# Power_Sheet.net
KiCad netlist of a schematic drawn in Altium Designer
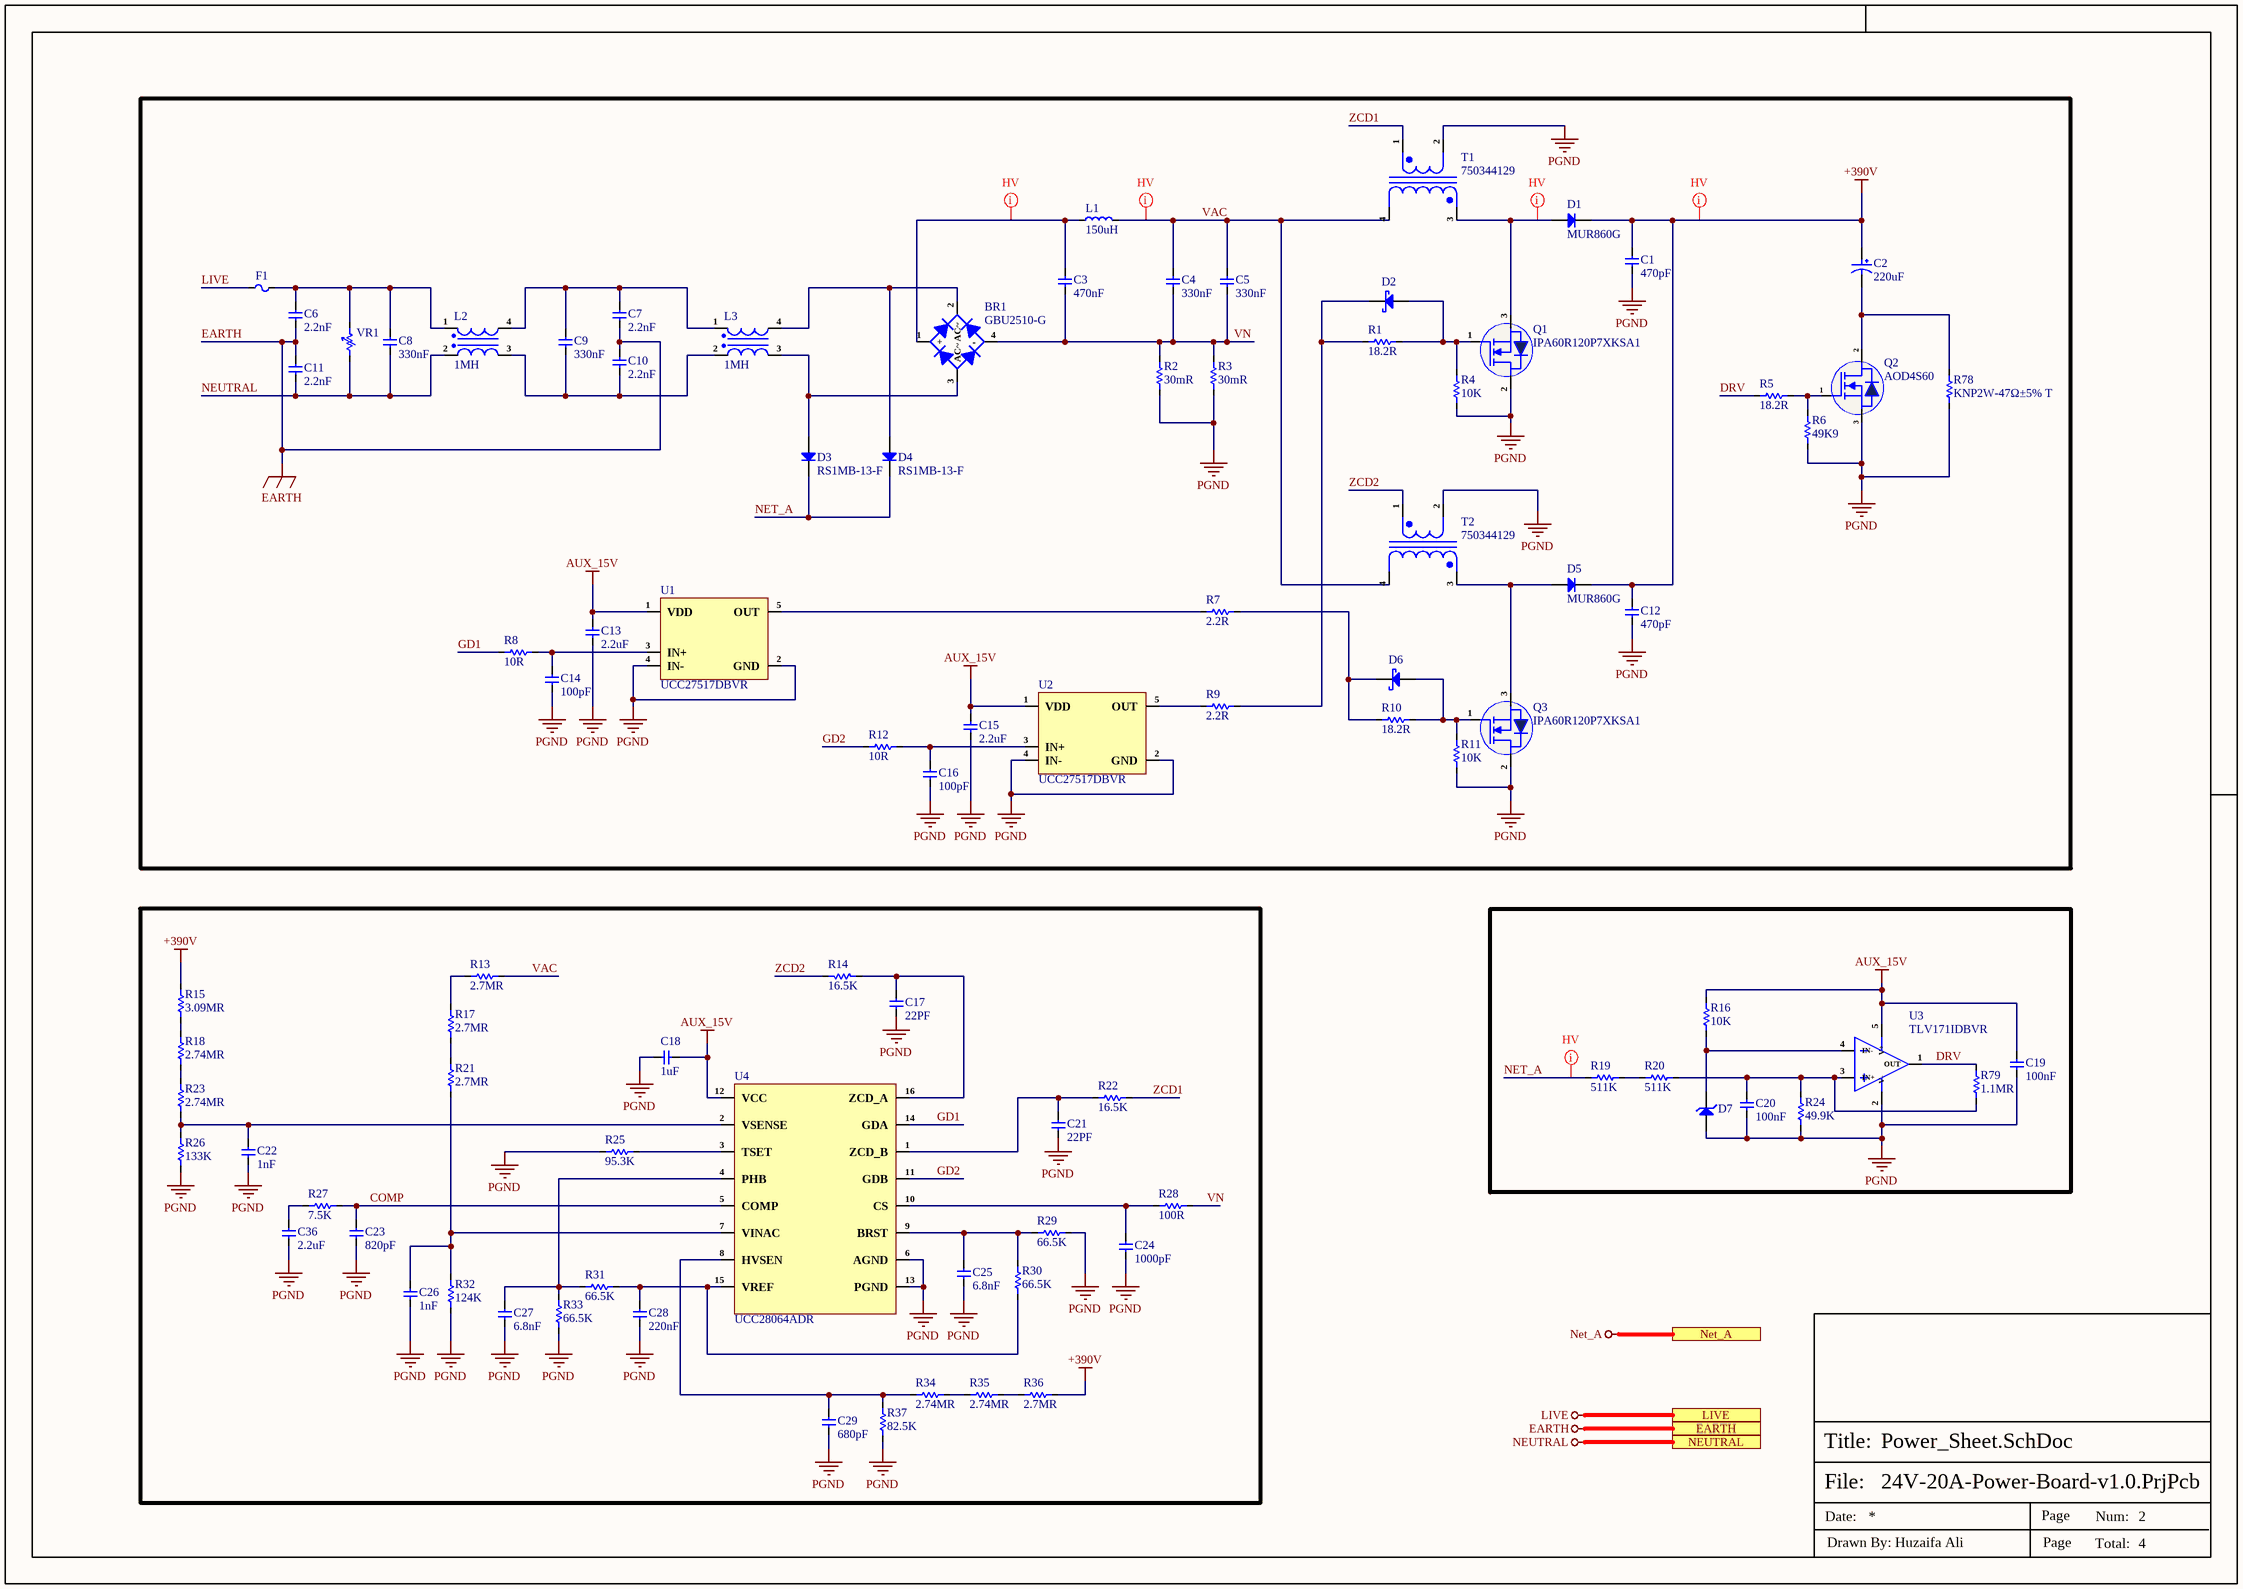
[diagram p0: Power_Sheet.SchDoc]

(export (version "E")
  (design (tool "Eeschema 10.0.6"))
  (components
    (comp (ref "BR1")
      (value "GBU2510-G")
      (footprint "GBU")
      (description "BRIDGE RECT 1PHASE 1KV 25A GBU")
      (fields (field (name "LCSC PART NUMBER") "C3012677") (field (name "MANUFACTURER") "Comchip"))
      (libsource (lib "eSpark Libraries") (part "GBU2510-G"))
    )
    (comp (ref "C1")
      (value "470pF")
      (footprint "Cap-0805")
      (description "CAP CER 470PF 500V X7R 0805")
      (fields (field (name "LCSC PART NUMBER") "C113867") (field (name "MANUFACTURER") "Yageo"))
      (libsource (lib "eSpark Libraries") (part "CC0805KRX7RBBB471"))
    )
    (comp (ref "C2")
      (value "220uF")
      (description "220uF 400V ±20% Plugin,D22xL40mm Aluminum Electrolytic Capacitors - Leaded ROHS")
      (fields
        (field (name "MANUFACTURER") "AISHI")
        (field (name "MANUFACTURER PART NUMBER") "EWH2GM221O40OT")
      )
      (libsource (lib "eSpark Libraries") (part "EWH2GM221O40OT"))
    )
    (comp (ref "C3")
      (value "470nF")
      (footprint "450MPK474J")
      (description "CAP FILM 0.47UF 5% 450VDC RADIAL")
      (fields (field (name "LCSC PART NUMBER") "C2798220") (field (name "MANUFACTURER") "Rubycon"))
      (libsource (lib "eSpark Libraries") (part "450MPK474J"))
    )
    (comp (ref "C4")
      (value "330nF")
      (footprint "MPP334J2J15AJ22800")
      (description "330nF -40℃~+105℃ ±5% 630V Plugin,P=15mm Polypropylene Film Capacitors (CBB) ROHS")
      (fields (field (name "LCSC PART NUMBER") "C506837") (field (name "MANUFACTURER") "KNSCHA"))
      (libsource (lib "eSpark Libraries") (part "MPP334J2J15AJ22800"))
    )
    (comp (ref "C5")
      (value "330nF")
      (footprint "MPP334J2J15AJ22800")
      (description "330nF -40℃~+105℃ ±5% 630V Plugin,P=15mm Polypropylene Film Capacitors (CBB) ROHS")
      (fields (field (name "LCSC PART NUMBER") "C506837") (field (name "MANUFACTURER") "KNSCHA"))
      (libsource (lib "eSpark Libraries") (part "MPP334J2J15AJ22800"))
    )
    (comp (ref "C6")
      (value "2.2nF")
      (footprint "AY1222M47Y5UC63L0")
      (description "CAP CER 2200PF 760VAC Y5U RADIAL")
      (fields (field (name "LCSC PART NUMBER") "C1620433"))
      (libsource (lib "eSpark Libraries") (part "AY1222M47Y5UC63L0"))
    )
    (comp (ref "C7")
      (value "2.2nF")
      (footprint "AY1222M47Y5UC63L0")
      (description "CAP CER 2200PF 760VAC Y5U RADIAL")
      (fields (field (name "LCSC PART NUMBER") "C1620433"))
      (libsource (lib "eSpark Libraries") (part "AY1222M47Y5UC63L0"))
    )
    (comp (ref "C8")
      (value "330nF")
      (description "330nF ±10% X2 Plugin,P=15mm Safety Capacitors ROHS")
      (fields
        (field (name "MANUFACTURER") "KNSCHA")
        (field (name "MANUFACTURER PART NUMBER") "MPX334K31D2KN15800")
      )
      (libsource (lib "eSpark Libraries") (part "MPX334K31D2KN15800"))
    )
    (comp (ref "C9")
      (value "330nF")
      (description "330nF ±10% X2 Plugin,P=15mm Safety Capacitors ROHS")
      (fields
        (field (name "MANUFACTURER") "KNSCHA")
        (field (name "MANUFACTURER PART NUMBER") "MPX334K31D2KN15800")
      )
      (libsource (lib "eSpark Libraries") (part "MPX334K31D2KN15800"))
    )
    (comp (ref "C10")
      (value "2.2nF")
      (footprint "AY1222M47Y5UC63L0")
      (description "CAP CER 2200PF 760VAC Y5U RADIAL")
      (fields (field (name "LCSC PART NUMBER") "C1620433"))
      (libsource (lib "eSpark Libraries") (part "AY1222M47Y5UC63L0"))
    )
    (comp (ref "C11")
      (value "2.2nF")
      (footprint "AY1222M47Y5UC63L0")
      (description "CAP CER 2200PF 760VAC Y5U RADIAL")
      (fields (field (name "LCSC PART NUMBER") "C1620433"))
      (libsource (lib "eSpark Libraries") (part "AY1222M47Y5UC63L0"))
    )
    (comp (ref "C12")
      (value "470pF")
      (footprint "Cap-0805")
      (description "CAP CER 470PF 500V X7R 0805")
      (fields (field (name "LCSC PART NUMBER") "C113867") (field (name "MANUFACTURER") "Yageo"))
      (libsource (lib "eSpark Libraries") (part "CC0805KRX7RBBB471"))
    )
    (comp (ref "C13")
      (value "2.2uF")
      (footprint "CAP-0603")
      (description "CAP CER 2.2UF 25V X5R 0603")
      (fields
        (field (name "MANUFACTURER") "Yageo")
        (field (name "MANUFACTURER PART NUMBER") "CC0603KRX5R8BB225")
      )
      (libsource (lib "eSpark Libraries") (part "CC0603KRX5R8BB225"))
    )
    (comp (ref "C14")
      (value "100pF")
      (footprint "Cap-0402")
      (description "CAP CER 100PF 50V C0G/NPO 0402")
      (fields
        (field (name "MANUFACTURER") "Yageo")
        (field (name "MANUFACTURER PART NUMBER") "CC0402JRNPO9BN101")
      )
      (libsource (lib "eSpark Libraries") (part "CC0402JRNPO9BN101"))
    )
    (comp (ref "C15")
      (value "2.2uF")
      (footprint "CAP-0603")
      (description "CAP CER 2.2UF 25V X5R 0603")
      (fields
        (field (name "MANUFACTURER") "Yageo")
        (field (name "MANUFACTURER PART NUMBER") "CC0603KRX5R8BB225")
      )
      (libsource (lib "eSpark Libraries") (part "CC0603KRX5R8BB225"))
    )
    (comp (ref "C16")
      (value "100pF")
      (footprint "Cap-0402")
      (description "CAP CER 100PF 50V C0G/NPO 0402")
      (fields
        (field (name "MANUFACTURER") "Yageo")
        (field (name "MANUFACTURER PART NUMBER") "CC0402JRNPO9BN101")
      )
      (libsource (lib "eSpark Libraries") (part "CC0402JRNPO9BN101"))
    )
    (comp (ref "C17")
      (value "22PF")
      (footprint "Cap-0402")
      (description "CAP CER 22PF 50V C0G/NPO 0402")
      (fields
        (field (name "MANUFACTURER") "Yageo")
        (field (name "MANUFACTURER PART NUMBER") "CC0402JRNPO9BN220")
      )
      (libsource (lib "eSpark Libraries") (part "CC0402JRNPO9BN220"))
    )
    (comp (ref "C18")
      (value "1uF")
      (footprint "Cap-0603")
      (description "CAP CER 1UF 25V X5R 0603")
      (fields
        (field (name "MANUFACTURER") "Yageo")
        (field (name "MANUFACTURER PART NUMBER") "CC0603KRX5R8BB105")
      )
      (libsource (lib "eSpark Libraries") (part "CC0603KRX5R8BB105"))
    )
    (comp (ref "C19")
      (value "100nF")
      (footprint "cap-0402")
      (description "CAP CER 0.1UF 50V X7R 0402")
      (fields
        (field (name "MANUFACTURER") "TDK")
        (field (name "MANUFACTURER PART NUMBER") "C1005X7R1H104KT000F")
      )
      (libsource (lib "eSpark Libraries") (part "C1005X7R1H104KT000F"))
    )
    (comp (ref "C20")
      (value "100nF")
      (footprint "cap-0402")
      (description "CAP CER 0.1UF 50V X7R 0402")
      (fields
        (field (name "MANUFACTURER") "TDK")
        (field (name "MANUFACTURER PART NUMBER") "C1005X7R1H104KT000F")
      )
      (libsource (lib "eSpark Libraries") (part "C1005X7R1H104KT000F"))
    )
    (comp (ref "C21")
      (value "22PF")
      (footprint "Cap-0402")
      (description "CAP CER 22PF 50V C0G/NPO 0402")
      (fields
        (field (name "MANUFACTURER") "Yageo")
        (field (name "MANUFACTURER PART NUMBER") "CC0402JRNPO9BN220")
      )
      (libsource (lib "eSpark Libraries") (part "CC0402JRNPO9BN220"))
    )
    (comp (ref "C22")
      (value "1nF")
      (footprint "Cap-0402")
      (description "CAP CER 1000PF 50V C0G/NP0 0402")
      (fields
        (field (name "MANUFACTURER") "Murata")
        (field (name "MANUFACTURER PART NUMBER") "GRM1555C1H102JA01D")
      )
      (libsource (lib "eSpark Libraries") (part "GRM1555C1H102JA01D"))
    )
    (comp (ref "C23")
      (value "820pF")
      (footprint "Cap-0603")
      (description "CAP CER 820PF 50V C0G/NPO 0603")
      (fields (field (name "LCSC PART NUMBER") "C107057") (field (name "MANUFACTURER") "Yageo"))
      (libsource (lib "eSpark Libraries") (part "CC0603JRNPO9BN821"))
    )
    (comp (ref "C24")
      (value "1000pF")
      (footprint "Cap-0603")
      (description "CAP CER 1000PF 50V C0G/NP0 0603")
      (fields
        (field (name "MANUFACTURER") "Samsung")
        (field (name "MANUFACTURER PART NUMBER") "CL10C102JB8NNNC")
      )
      (libsource (lib "eSpark Libraries") (part "CL10C102JB8NNNC"))
    )
    (comp (ref "C25")
      (value "6.8nF")
      (footprint "Cap-0603")
      (description "50V 6.8nF X7R ±10% 0603")
      (fields (field (name "MANUFACTURER") "FH") (field (name "MANUFACTURER PART NUMBER") "0603B682K500NT"))
      (libsource (lib "eSpark Libraries") (part "0603B682K500NT"))
    )
    (comp (ref "C26")
      (value "1nF")
      (footprint "Cap-0603")
      (description "CAP CER 1000PF 100V X7R 0603")
      (fields (field (name "LCSC PART NUMBER") "C2179225") (field (name "MANUFACTURER") "Kyocera AVX"))
      (libsource (lib "eSpark Libraries") (part "06031C102JAT2A"))
    )
    (comp (ref "C27")
      (value "6.8nF")
      (footprint "Cap-0603")
      (description "50V 6.8nF X7R ±10% 0603")
      (fields (field (name "MANUFACTURER") "FH") (field (name "MANUFACTURER PART NUMBER") "0603B682K500NT"))
      (libsource (lib "eSpark Libraries") (part "0603B682K500NT"))
    )
    (comp (ref "C28")
      (value "220nF")
      (footprint "Cap-1206")
      (description "CAP CER 0.22UF 50V X7R 1206")
      (fields
        (field (name "MANUFACTURER") "Yageo")
        (field (name "MANUFACTURER PART NUMBER") "CC1206JKX7R9BB224")
      )
      (libsource (lib "eSpark Libraries") (part "CC1206JKX7R9BB224"))
    )
    (comp (ref "C29")
      (value "680pF")
      (footprint "Cap-0603")
      (description "CAP CER 680PF 50V C0G/NPO 0603")
      (fields (field (name "LCSC PART NUMBER") "C107055") (field (name "MANUFACTURER") "Yageo"))
      (libsource (lib "eSpark Libraries") (part "CC0603JRNPO9BN681"))
    )
    (comp (ref "C36")
      (value "2.2uF")
      (footprint "Cap-0805")
      (description "CAP CER 2.2UF 25V X5R 0805")
      (fields
        (field (name "MANUFACTURER") "Yageo")
        (field (name "MANUFACTURER PART NUMBER") "CC0805KKX5R8BB225")
      )
      (libsource (lib "eSpark Libraries") (part "CC0805KKX5R8BB225"))
    )
    (comp (ref "D1")
      (value "MUR860G")
      (footprint "TO-220-2")
      (description "DIODE GEN PURP 600V 8A TO220-2")
      (fields (field (name "LCSC PART NUMBER") "C50428") (field (name "MANUFACTURER") "ON Semiconductor"))
      (libsource (lib "eSpark Libraries") (part "MUR860G"))
    )
    (comp (ref "D2")
      (value "BAT54HT1G")
      (footprint "SOD-323")
      (description "30V Independent Type 1V@100mA 200mA SOD-323 Schottky Diodes ROHS")
      (fields (field (name "MANUFACTURER") "FUXINSEMI") (field (name "LCSC PART NUMBER") "C7422626"))
      (libsource (lib "eSpark Libraries") (part "BAT54HT1G"))
    )
    (comp (ref "D3")
      (value "RS1MB-13-F")
      (footprint "SMB_")
      (description "DIODE GEN PURP 1KV 1A SMB")
      (fields (field (name "LCSC PART NUMBER") "C154864") (field (name "MANUFACTURER") "Diodes"))
      (libsource (lib "eSpark Libraries") (part "RS1MB-13-F"))
    )
    (comp (ref "D4")
      (value "RS1MB-13-F")
      (footprint "SMB_")
      (description "DIODE GEN PURP 1KV 1A SMB")
      (fields (field (name "LCSC PART NUMBER") "C154864") (field (name "MANUFACTURER") "Diodes"))
      (libsource (lib "eSpark Libraries") (part "RS1MB-13-F"))
    )
    (comp (ref "D5")
      (value "MUR860G")
      (footprint "TO-220-2")
      (description "DIODE GEN PURP 600V 8A TO220-2")
      (fields (field (name "LCSC PART NUMBER") "C50428") (field (name "MANUFACTURER") "ON Semiconductor"))
      (libsource (lib "eSpark Libraries") (part "MUR860G"))
    )
    (comp (ref "D6")
      (value "BAT54HT1G")
      (footprint "SOD-323")
      (description "30V Independent Type 1V@100mA 200mA SOD-323 Schottky Diodes ROHS")
      (fields (field (name "MANUFACTURER") "FUXINSEMI") (field (name "LCSC PART NUMBER") "C7422626"))
      (libsource (lib "eSpark Libraries") (part "BAT54HT1G"))
    )
    (comp (ref "D7")
      (value "BZT52C5V1S-7-F")
      (footprint "SOD-323")
      (description "DIODE ZENER 5.1V 200MW SOD323")
      (fields (field (name "LCSC PART NUMBER") "C151348") (field (name "MANUFACTURER") "Diodes"))
      (libsource (lib "eSpark Libraries") (part "BZT52C5V1S-7-F"))
    )
    (comp (ref "F1")
      (value "0501010.WR1")
      (footprint "Fuse 1206 (3216 Metric)")
      (description "150A SMD Fuse 10A 32V 1206 Disposable fuses ROHS")
      (fields (field (name "MANUFACTURER") "Littelfuse") (field (name "LCSC PART NUMBER") "C207003"))
      (libsource (lib "eSpark Libraries") (part "0501010.WR1"))
    )
    (comp (ref "L1")
      (value "150uH")
      (footprint "7447076")
      (description "FIXED IND 150UH 5A 45 MOHM TH")
      (fields
        (field (name "MANUFACTURER") "Wurth Electronics")
        (field (name "MANUFACTURER PART NUMBER") "7447076")
      )
      (libsource (lib "eSpark Libraries") (part "7447076"))
    )
    (comp (ref "L2")
      (value "1MH")
      (footprint "7448031501")
      (description "CMC 1MH 15A 2LN TH")
      (fields
        (field (name "MANUFACTURER") "Wurth Electronics")
        (field (name "MANUFACTURER PART NUMBER") "7448031501")
      )
      (libsource (lib "eSpark Libraries") (part "7448031501"))
    )
    (comp (ref "L3")
      (value "1MH")
      (footprint "7448031501")
      (description "CMC 1MH 15A 2LN TH")
      (fields
        (field (name "MANUFACTURER") "Wurth Electronics")
        (field (name "MANUFACTURER PART NUMBER") "7448031501")
      )
      (libsource (lib "eSpark Libraries") (part "7448031501"))
    )
    (comp (ref "Q1")
      (value "IPA60R120P7XKSA1")
      (footprint "TO-220-3")
      (description "MOSFET N-CH 600V 26A TO220")
      (fields (field (name "MANUFACTURER") "Infineon"))
      (libsource (lib "eSpark Libraries") (part "IPA60R120P7XKSA1"))
    )
    (comp (ref "Q2")
      (value "AOD4S60")
      (footprint "TO-252-2L")
      (description "MOSFET N-CH 600V 4A TO252")
      (fields (field (name "MANUFACTURER") "Alpha & Omega Semiconductor"))
      (libsource (lib "eSpark Libraries") (part "AOD4S60"))
    )
    (comp (ref "Q3")
      (value "IPA60R120P7XKSA1")
      (footprint "TO-220-3")
      (description "MOSFET N-CH 600V 26A TO220")
      (fields (field (name "MANUFACTURER") "Infineon"))
      (libsource (lib "eSpark Libraries") (part "IPA60R120P7XKSA1"))
    )
    (comp (ref "R1")
      (value "18.2R")
      (footprint "RES-0805")
      (description "125mW Thick Film Resistors 150V ±100ppm/℃ ±1% 18.2Ω 0805 Chip Resistor - Surface Mount ROHS")
      (libsource (lib "eSpark Libraries") (part "FRC0805F18R2TS"))
    )
    (comp (ref "R2")
      (value "30mR")
      (footprint "RES-2512")
      (description "RES 0.03 OHM 1% 2W 2512")
      (fields (field (name "LCSC PART NUMBER") "C728311") (field (name "MANUFACTURER") "Yageo"))
      (libsource (lib "eSpark Libraries") (part "PA2512FKE7W0R03E"))
    )
    (comp (ref "R3")
      (value "30mR")
      (footprint "RES-2512")
      (description "RES 0.03 OHM 1% 2W 2512")
      (fields (field (name "LCSC PART NUMBER") "C728311") (field (name "MANUFACTURER") "Yageo"))
      (libsource (lib "eSpark Libraries") (part "PA2512FKE7W0R03E"))
    )
    (comp (ref "R4")
      (value "10K")
      (footprint "Res-0603")
      (description "RES SMD 10K Ohm 1% 1/10W 0603")
      (fields
        (field (name "MANUFACTURER") "Yageo")
        (field (name "MANUFACTURER PART NUMBER") "RC0603FR-0710KL")
      )
      (libsource (lib "eSpark Libraries") (part "RC0603FR-0710KL"))
    )
    (comp (ref "R5")
      (value "18.2R")
      (footprint "RES-0805")
      (description "125mW Thick Film Resistors 150V ±100ppm/℃ ±1% 18.2Ω 0805 Chip Resistor - Surface Mount ROHS")
      (libsource (lib "eSpark Libraries") (part "FRC0805F18R2TS"))
    )
    (comp (ref "R6")
      (value "49K9")
      (footprint "Res-0603")
      (description "RES 49.9K OHM 1% 1/10W 0603")
      (fields
        (field (name "MANUFACTURER") "Yageo")
        (field (name "MANUFACTURER PART NUMBER") "RC0603FR-0749K9L")
      )
      (libsource (lib "eSpark Libraries") (part "RC0603FR-0749K9L"))
    )
    (comp (ref "R7")
      (value "2.2R")
      (footprint "Res-0603")
      (description "RES 2.2 OHM 1% 1/10W 0603")
      (fields (field (name "LCSC PART NUMBER") "C112307") (field (name "MANUFACTURER") "Yageo"))
      (libsource (lib "eSpark Libraries") (part "RC0603FR-072R2L"))
    )
    (comp (ref "R8")
      (value "10R")
      (footprint "Res-0402")
      (description "RES SMD 10 OHM 1% 1/5W 0402")
      (fields
        (field (name "MANUFACTURER") "Vishay Dale")
        (field (name "MANUFACTURER PART NUMBER") "CRCW040210R0FKEDHP")
      )
      (libsource (lib "eSpark Libraries") (part "CRCW040210R0FKEDHP"))
    )
    (comp (ref "R9")
      (value "2.2R")
      (footprint "Res-0603")
      (description "RES 2.2 OHM 1% 1/10W 0603")
      (fields (field (name "LCSC PART NUMBER") "C112307") (field (name "MANUFACTURER") "Yageo"))
      (libsource (lib "eSpark Libraries") (part "RC0603FR-072R2L"))
    )
    (comp (ref "R10")
      (value "18.2R")
      (footprint "RES-0805")
      (description "125mW Thick Film Resistors 150V ±100ppm/℃ ±1% 18.2Ω 0805 Chip Resistor - Surface Mount ROHS")
      (libsource (lib "eSpark Libraries") (part "FRC0805F18R2TS"))
    )
    (comp (ref "R11")
      (value "10K")
      (footprint "Res-0603")
      (description "RES SMD 10K Ohm 1% 1/10W 0603")
      (fields
        (field (name "MANUFACTURER") "Yageo")
        (field (name "MANUFACTURER PART NUMBER") "RC0603FR-0710KL")
      )
      (libsource (lib "eSpark Libraries") (part "RC0603FR-0710KL"))
    )
    (comp (ref "R12")
      (value "10R")
      (footprint "Res-0402")
      (description "RES SMD 10 OHM 1% 1/5W 0402")
      (fields
        (field (name "MANUFACTURER") "Vishay Dale")
        (field (name "MANUFACTURER PART NUMBER") "CRCW040210R0FKEDHP")
      )
      (libsource (lib "eSpark Libraries") (part "CRCW040210R0FKEDHP"))
    )
    (comp (ref "R13")
      (value "2.7MR")
      (footprint "Res-1206")
      (description "250mW 200V ±1% 2.7MΩ 1206 Chip Resistor - Surface Mount ROHS")
      (fields
        (field (name "MANUFACTURER") "LIZ Elec")
        (field (name "MANUFACTURER PART NUMBER") "CR1206F42704G")
      )
      (libsource (lib "eSpark Libraries") (part "CR1206F42704G"))
    )
    (comp (ref "R14")
      (value "16.5K")
      (footprint "Res-0603")
      (description "100mW Thick Film Resistors 75V ±100ppm/℃ ±1% 16.5kΩ 0603 Chip Resistor - Surface Mount ROHS")
      (fields
        (field (name "MANUFACTURER") "FOJAN")
        (field (name "MANUFACTURER PART NUMBER") "FRC0603F1652TS")
      )
      (libsource (lib "eSpark Libraries") (part "FRC0603F1652TS"))
    )
    (comp (ref "R15")
      (value "3.09MR")
      (footprint "Res-1206")
      (description "RES 3.09M OHM 1% 1/4W 1206")
      (fields (field (name "LCSC PART NUMBER") "C488771") (field (name "MANUFACTURER") "Yageo"))
      (libsource (lib "eSpark Libraries") (part "RC1206FR-073M09L"))
    )
    (comp (ref "R16")
      (value "10K")
      (footprint "Res-0603")
      (description "RES SMD 10K OHM 0.1% 1/10W 0603")
      (fields
        (field (name "MANUFACTURER") "Yageo")
        (field (name "MANUFACTURER PART NUMBER") "RT0603BRD0710KL")
      )
      (libsource (lib "eSpark Libraries") (part "RT0603BRD0710KL"))
    )
    (comp (ref "R17")
      (value "2.7MR")
      (footprint "Res-1206")
      (description "250mW 200V ±1% 2.7MΩ 1206 Chip Resistor - Surface Mount ROHS")
      (fields
        (field (name "MANUFACTURER") "LIZ Elec")
        (field (name "MANUFACTURER PART NUMBER") "CR1206F42704G")
      )
      (libsource (lib "eSpark Libraries") (part "CR1206F42704G"))
    )
    (comp (ref "R18")
      (value "2.74MR")
      (footprint "RES-0805")
      (description "RES 2.74M OHM 1% 1/8W 0805")
      (fields (field (name "LCSC PART NUMBER") "C483055") (field (name "MANUFACTURER") "Yageo"))
      (libsource (lib "eSpark Libraries") (part "RC0805FR-072M74L"))
    )
    (comp (ref "R19")
      (value "511K")
      (footprint "Res-1206")
      (description "250mW Thick Film Resistors 200V ±100ppm/℃ ±1% 511kΩ 1206 Chip Resistor - Surface Mount ROHS")
      (fields
        (field (name "MANUFACTURER") "Ever Ohms Tech")
        (field (name "MANUFACTURER PART NUMBER") "CR1206F511KP05Z")
      )
      (libsource (lib "eSpark Libraries") (part "CR1206F511KP05Z"))
    )
    (comp (ref "R20")
      (value "511K")
      (footprint "Res-1206")
      (description "250mW Thick Film Resistors 200V ±100ppm/℃ ±1% 511kΩ 1206 Chip Resistor - Surface Mount ROHS")
      (fields
        (field (name "MANUFACTURER") "Ever Ohms Tech")
        (field (name "MANUFACTURER PART NUMBER") "CR1206F511KP05Z")
      )
      (libsource (lib "eSpark Libraries") (part "CR1206F511KP05Z"))
    )
    (comp (ref "R21")
      (value "2.7MR")
      (footprint "Res-1206")
      (description "250mW 200V ±1% 2.7MΩ 1206 Chip Resistor - Surface Mount ROHS")
      (fields
        (field (name "MANUFACTURER") "LIZ Elec")
        (field (name "MANUFACTURER PART NUMBER") "CR1206F42704G")
      )
      (libsource (lib "eSpark Libraries") (part "CR1206F42704G"))
    )
    (comp (ref "R22")
      (value "16.5K")
      (footprint "Res-0603")
      (description "100mW Thick Film Resistors 75V ±100ppm/℃ ±1% 16.5kΩ 0603 Chip Resistor - Surface Mount ROHS")
      (fields
        (field (name "MANUFACTURER") "FOJAN")
        (field (name "MANUFACTURER PART NUMBER") "FRC0603F1652TS")
      )
      (libsource (lib "eSpark Libraries") (part "FRC0603F1652TS"))
    )
    (comp (ref "R23")
      (value "2.74MR")
      (footprint "RES-0805")
      (description "RES 2.74M OHM 1% 1/8W 0805")
      (fields (field (name "LCSC PART NUMBER") "C483055") (field (name "MANUFACTURER") "Yageo"))
      (libsource (lib "eSpark Libraries") (part "RC0805FR-072M74L"))
    )
    (comp (ref "R24")
      (value "49.9K")
      (footprint "RES-0805")
      (description "RES 49.9K OHM 1% 1/8W 0805")
      (fields
        (field (name "MANUFACTURER") "Yageo")
        (field (name "MANUFACTURER PART NUMBER") "RC0805FR-0749K9L")
      )
      (libsource (lib "eSpark Libraries") (part "RC0805FR-0749K9L"))
    )
    (comp (ref "R25")
      (value "95.3K")
      (footprint "Res-0402")
      (description "RES 95.3K OHM 1% 1/16W 0402")
      (fields
        (field (name "MANUFACTURER") "Yageo")
        (field (name "MANUFACTURER PART NUMBER") "RC0402FR-0795K3L")
      )
      (libsource (lib "eSpark Libraries") (part "RC0402FR-0795K3L"))
    )
    (comp (ref "R26")
      (value "133K")
      (footprint "Res-0603")
      (description "100mW Thick Film Resistors 75V ±100ppm/℃ ±1% 133kΩ 0603 Chip Resistor - Surface Mount ROHS")
      (fields
        (field (name "MANUFACTURER") "UNI-ROYAL")
        (field (name "MANUFACTURER PART NUMBER") "0603WAF1333T5E")
      )
      (libsource (lib "eSpark Libraries") (part "0603WAF1333T5E"))
    )
    (comp (ref "R27")
      (value "7.5K")
      (footprint "Res-0603")
      (description "RES SMD 7.5K OHM 0.1% 1/10W 0603")
      (fields
        (field (name "MANUFACTURER") "Yageo")
        (field (name "MANUFACTURER PART NUMBER") "RT0603BRD077K5L")
      )
      (libsource (lib "eSpark Libraries") (part "RT0603BRD077K5L"))
    )
    (comp (ref "R28")
      (value "100R")
      (footprint "Res-0603")
      (description "RES SMD 100 OHM 1% 1/10W 0603")
      (fields (field (name "LCSC PART NUMBER") "C844513") (field (name "TOLERANCE") "1%"))
      (libsource (lib "eSpark Libraries") (part "CRCW0603100RFKEB"))
    )
    (comp (ref "R29")
      (value "66.5K")
      (footprint "Res-0603")
      (description "100mW Thick Film Resistors 75V ±100ppm/℃ ±1% 66.5kΩ 0603 Chip Resistor - Surface Mount ROHS")
      (fields
        (field (name "MANUFACTURER") "FOJAN")
        (field (name "MANUFACTURER PART NUMBER") "FRC0603F6652TS")
      )
      (libsource (lib "eSpark Libraries") (part "FRC0603F6652TS"))
    )
    (comp (ref "R30")
      (value "66.5K")
      (footprint "Res-0603")
      (description "100mW Thick Film Resistors 75V ±100ppm/℃ ±1% 66.5kΩ 0603 Chip Resistor - Surface Mount ROHS")
      (fields
        (field (name "MANUFACTURER") "FOJAN")
        (field (name "MANUFACTURER PART NUMBER") "FRC0603F6652TS")
      )
      (libsource (lib "eSpark Libraries") (part "FRC0603F6652TS"))
    )
    (comp (ref "R31")
      (value "66.5K")
      (footprint "Res-0603")
      (description "100mW Thick Film Resistors 75V ±100ppm/℃ ±1% 66.5kΩ 0603 Chip Resistor - Surface Mount ROHS")
      (fields
        (field (name "MANUFACTURER") "FOJAN")
        (field (name "MANUFACTURER PART NUMBER") "FRC0603F6652TS")
      )
      (libsource (lib "eSpark Libraries") (part "FRC0603F6652TS"))
    )
    (comp (ref "R32")
      (value "124K")
      (footprint "Res-0603")
      (description "RES SMD 124K OHM 1% 1/10W 0603")
      (fields
        (field (name "MANUFACTURER") "Yageo")
        (field (name "MANUFACTURER PART NUMBER") "AC0603FR-07124KL")
      )
      (libsource (lib "eSpark Libraries") (part "AC0603FR-07124KL"))
    )
    (comp (ref "R33")
      (value "66.5K")
      (footprint "Res-0603")
      (description "100mW Thick Film Resistors 75V ±100ppm/℃ ±1% 66.5kΩ 0603 Chip Resistor - Surface Mount ROHS")
      (fields
        (field (name "MANUFACTURER") "FOJAN")
        (field (name "MANUFACTURER PART NUMBER") "FRC0603F6652TS")
      )
      (libsource (lib "eSpark Libraries") (part "FRC0603F6652TS"))
    )
    (comp (ref "R34")
      (value "2.74MR")
      (footprint "RES-0805")
      (description "RES 2.74M OHM 1% 1/8W 0805")
      (fields (field (name "LCSC PART NUMBER") "C483055") (field (name "MANUFACTURER") "Yageo"))
      (libsource (lib "eSpark Libraries") (part "RC0805FR-072M74L"))
    )
    (comp (ref "R35")
      (value "2.74MR")
      (footprint "RES-0805")
      (description "RES 2.74M OHM 1% 1/8W 0805")
      (fields (field (name "LCSC PART NUMBER") "C483055") (field (name "MANUFACTURER") "Yageo"))
      (libsource (lib "eSpark Libraries") (part "RC0805FR-072M74L"))
    )
    (comp (ref "R36")
      (value "2.7MR")
      (footprint "Res-1206")
      (description "250mW 200V ±1% 2.7MΩ 1206 Chip Resistor - Surface Mount ROHS")
      (fields
        (field (name "MANUFACTURER") "LIZ Elec")
        (field (name "MANUFACTURER PART NUMBER") "CR1206F42704G")
      )
      (libsource (lib "eSpark Libraries") (part "CR1206F42704G"))
    )
    (comp (ref "R37")
      (value "82.5K")
      (footprint "Res-0603")
      (description "RES 82.5K OHM 1% 1/10W 0603")
      (fields (field (name "LCSC PART NUMBER") "C185310") (field (name "MANUFACTURER") "Yageo"))
      (libsource (lib "eSpark Libraries") (part "RC0603FR-0782K5L"))
    )
    (comp (ref "R78")
      (value "KNP2W-47Ω±5% T")
      (footprint "KNP2W-47O±5")
      (description "Wirewound Resistors 47Ω 2W ±350ppm/℃ ±5% Plugin,D5xL15.5mm Through Hole Resistors ROHS")
      (fields
        (field (name "MANUFACTURER") "CCO(Chian Chia Elec)")
        (field (name "LCSC PART NUMBER") "C122138")
      )
      (libsource (lib "eSpark Libraries") (part "1/4 watt Resistor"))
    )
    (comp (ref "R79")
      (value "1.1MR")
      (footprint "Res-0603")
      (description "100mW Thick Film Resistors 75V ±100ppm/℃ ±1% 1.1MΩ 0603 Chip Resistor - Surface Mount ROHS")
      (fields (field (name "LCSC PART NUMBER") "C13314") (field (name "MANUFACTURER") "Uniroyal"))
      (libsource (lib "eSpark Libraries") (part "0603WAF1104T5E"))
    )
    (comp (ref "T1")
      (value "750344129")
      (fields
        (field (name "MANUFACTURER") "Wurth Electronik")
        (field (name "MANUFACTURER PART NUMBER") "750344127")
      )
      (libsource (lib "eSpark Libraries") (part "750344129"))
    )
    (comp (ref "T2")
      (value "750344129")
      (fields
        (field (name "MANUFACTURER") "Wurth Electronik")
        (field (name "MANUFACTURER PART NUMBER") "750344127")
      )
      (libsource (lib "eSpark Libraries") (part "750344129"))
    )
    (comp (ref "U1")
      (value "UCC27517DBVR")
      (footprint "SOT-23-5")
      (description "IC GATE DRVR LOW-SIDE SOT23-5")
      (fields (field (name "LCSC PART NUMBER") "C99395") (field (name "MANUFACTURER") "Texas Instruments"))
      (libsource (lib "eSpark Libraries") (part "UCC27517DBVR"))
    )
    (comp (ref "U2")
      (value "UCC27517DBVR")
      (footprint "SOT-23-5")
      (description "IC GATE DRVR LOW-SIDE SOT23-5")
      (fields (field (name "LCSC PART NUMBER") "C99395") (field (name "MANUFACTURER") "Texas Instruments"))
      (libsource (lib "eSpark Libraries") (part "UCC27517DBVR"))
    )
    (comp (ref "U3")
      (value "TLV171IDBVR")
      (footprint "SOT-23-5")
      (description "IC OPAMP GP 1 CIRCUIT SOT23-5")
      (fields (field (name "LCSC PART NUMBER") "C2864299") (field (name "MANUFACTURER") "Texas Instruments"))
      (libsource (lib "eSpark Libraries") (part "TLV171IDBVR"))
    )
    (comp (ref "U4")
      (value "UCC28064ADR")
      (footprint "SOIC-16")
      (description "IC PFC CTR TRANS 45KHZ 16SOIC")
      (fields (field (name "LCSC PART NUMBER") "C882391") (field (name "MANUFACTURER") "Texas Instruments"))
      (libsource (lib "eSpark Libraries") (part "UCC28064ADR"))
    )
    (comp (ref "VR1")
      (value "B72210S2271K101")
      (footprint "B72210S2271K101")
      (description "VARISTOR 430V 3.5KA DISC 10MM")
      (fields (field (name "LCSC PART NUMBER") "C210564") (field (name "MANUFACTURER") "TDK EPCOS"))
      (libsource (lib "eSpark Libraries") (part "B72210S2271K101"))
    )
  )
  (nets
    (net (code "1") (name "+390V") (class "Default")
      (node (ref "C1") (pin "2") (pinfunction "2_2") (pintype "passive"))
      (node (ref "C12") (pin "2") (pinfunction "2_2") (pintype "passive"))
      (node (ref "C2") (pin "1") (pintype "passive"))
      (node (ref "D1") (pin "1") (pinfunction "K_1") (pintype "passive"))
      (node (ref "D5") (pin "1") (pinfunction "K_1") (pintype "passive"))
      (node (ref "R15") (pin "2") (pinfunction "2_2") (pintype "passive"))
      (node (ref "R36") (pin "2") (pinfunction "2_2") (pintype "passive"))
    )
    (net (code "2") (name "/COMP") (class "Default")
      (node (ref "C23") (pin "2") (pinfunction "2_2") (pintype "passive"))
      (node (ref "R27") (pin "2") (pinfunction "2_2") (pintype "passive"))
      (node (ref "U4") (pin "5") (pinfunction "COMP_5") (pintype "passive"))
    )
    (net (code "3") (name "/DRV") (class "Default")
      (node (ref "R5") (pin "1") (pinfunction "1_1") (pintype "passive"))
      (node (ref "R79") (pin "2") (pinfunction "2_2") (pintype "passive"))
      (node (ref "U3") (pin "1") (pinfunction "OUT_1") (pintype "passive"))
    )
    (net (code "4") (name "/GD1") (class "Default")
      (node (ref "R8") (pin "1") (pinfunction "1_1") (pintype "passive"))
      (node (ref "U4") (pin "14") (pinfunction "GDA_14") (pintype "passive"))
    )
    (net (code "5") (name "/GD2") (class "Default")
      (node (ref "R12") (pin "1") (pinfunction "1_1") (pintype "passive"))
      (node (ref "U4") (pin "11") (pinfunction "GDB_11") (pintype "passive"))
    )
    (net (code "6") (name "/NET_A") (class "Default")
      (node (ref "D3") (pin "2") (pinfunction "K_2") (pintype "passive"))
      (node (ref "D4") (pin "2") (pinfunction "K_2") (pintype "passive"))
      (node (ref "R19") (pin "1") (pinfunction "1_1") (pintype "passive"))
    )
    (net (code "7") (name "/VAC") (class "Default")
      (node (ref "C4") (pin "2") (pinfunction "2_2") (pintype "passive"))
      (node (ref "C5") (pin "2") (pinfunction "2_2") (pintype "passive"))
      (node (ref "L1") (pin "2") (pinfunction "2_2") (pintype "passive"))
      (node (ref "R13") (pin "1") (pinfunction "1_1") (pintype "passive"))
      (node (ref "T1") (pin "4") (pintype "passive"))
      (node (ref "T2") (pin "4") (pintype "passive"))
    )
    (net (code "8") (name "/VN") (class "Default")
      (node (ref "BR1") (pin "4") (pinfunction "-_4") (pintype "passive"))
      (node (ref "C3") (pin "1") (pinfunction "1_1") (pintype "passive"))
      (node (ref "C4") (pin "1") (pinfunction "1_1") (pintype "passive"))
      (node (ref "C5") (pin "1") (pinfunction "1_1") (pintype "passive"))
      (node (ref "R2") (pin "2") (pinfunction "2_2") (pintype "passive"))
      (node (ref "R28") (pin "2") (pinfunction "2_2") (pintype "passive"))
      (node (ref "R3") (pin "2") (pinfunction "2_2") (pintype "passive"))
    )
    (net (code "9") (name "/ZCD1") (class "Default")
      (node (ref "R22") (pin "2") (pinfunction "2_2") (pintype "passive"))
      (node (ref "T1") (pin "1") (pinfunction "1_1") (pintype "passive"))
    )
    (net (code "10") (name "/ZCD2") (class "Default")
      (node (ref "R14") (pin "2") (pinfunction "2_2") (pintype "passive"))
      (node (ref "T2") (pin "1") (pinfunction "1_1") (pintype "passive"))
    )
    (net (code "11") (name "AUX_15V") (class "Default")
      (node (ref "C13") (pin "2") (pinfunction "2_2") (pintype "passive"))
      (node (ref "C15") (pin "2") (pinfunction "2_2") (pintype "passive"))
      (node (ref "C18") (pin "2") (pinfunction "2_2") (pintype "passive"))
      (node (ref "C19") (pin "2") (pinfunction "2_2") (pintype "passive"))
      (node (ref "R16") (pin "2") (pinfunction "2_2") (pintype "passive"))
      (node (ref "U1") (pin "1") (pinfunction "VDD_1") (pintype "passive"))
      (node (ref "U2") (pin "1") (pinfunction "VDD_1") (pintype "passive"))
      (node (ref "U3") (pin "5") (pinfunction "V+_5") (pintype "power_in"))
      (node (ref "U4") (pin "12") (pinfunction "VCC_12") (pintype "passive"))
    )
    (net (code "12") (name "EARTH") (class "Default")
      (node (ref "C10") (pin "2") (pinfunction "2_2") (pintype "passive"))
      (node (ref "C11") (pin "2") (pinfunction "2_2") (pintype "passive"))
      (node (ref "C6") (pin "1") (pinfunction "1_1") (pintype "passive"))
      (node (ref "C7") (pin "1") (pinfunction "1_1") (pintype "passive"))
    )
    (net (code "13") (name "LIVE") (class "Default")
      (node (ref "F1") (pin "1") (pinfunction "1_1") (pintype "passive"))
    )
    (net (code "14") (name "NEUTRAL") (class "Default")
      (node (ref "C11") (pin "1") (pinfunction "1_1") (pintype "passive"))
      (node (ref "C8") (pin "1") (pinfunction "1_1") (pintype "passive"))
      (node (ref "L2") (pin "2") (pinfunction "2_2") (pintype "passive"))
      (node (ref "VR1") (pin "1") (pinfunction "1_1") (pintype "passive"))
    )
    (net (code "15") (name "Net-(BR1-+)") (class "Default")
      (node (ref "BR1") (pin "1") (pinfunction "+_1") (pintype "passive"))
      (node (ref "C3") (pin "2") (pinfunction "2_2") (pintype "passive"))
      (node (ref "L1") (pin "1") (pinfunction "1_1") (pintype "passive"))
    )
    (net (code "16") (name "Net-(C6-Pad2)") (class "Default")
      (node (ref "C6") (pin "2") (pinfunction "2_2") (pintype "passive"))
      (node (ref "C8") (pin "2") (pinfunction "2_2") (pintype "passive"))
      (node (ref "F1") (pin "2") (pinfunction "2_2") (pintype "passive"))
      (node (ref "L2") (pin "1") (pinfunction "1_1") (pintype "passive"))
      (node (ref "VR1") (pin "2") (pinfunction "2_2") (pintype "passive"))
    )
    (net (code "17") (name "Net-(C7-Pad2)") (class "Default")
      (node (ref "C7") (pin "2") (pinfunction "2_2") (pintype "passive"))
      (node (ref "C9") (pin "2") (pinfunction "2_2") (pintype "passive"))
      (node (ref "L2") (pin "4") (pinfunction "4_4") (pintype "passive"))
      (node (ref "L3") (pin "1") (pinfunction "1_1") (pintype "passive"))
    )
    (net (code "18") (name "Net-(C10-Pad1)") (class "Default")
      (node (ref "C10") (pin "1") (pinfunction "1_1") (pintype "passive"))
      (node (ref "C9") (pin "1") (pinfunction "1_1") (pintype "passive"))
      (node (ref "L2") (pin "3") (pinfunction "3_3") (pintype "passive"))
      (node (ref "L3") (pin "2") (pinfunction "2_2") (pintype "passive"))
    )
    (net (code "19") (name "Net-(C36-Pad2)") (class "Default")
      (node (ref "C36") (pin "2") (pinfunction "2_2") (pintype "passive"))
      (node (ref "R27") (pin "1") (pinfunction "1_1") (pintype "passive"))
    )
    (net (code "20") (name "Net-(D1-A)") (class "Default")
      (node (ref "D1") (pin "2") (pinfunction "A_2") (pintype "passive"))
      (node (ref "Q1") (pin "3") (pinfunction "S_3") (pintype "passive"))
      (node (ref "T1") (pin "3") (pinfunction "3_3") (pintype "passive"))
    )
    (net (code "21") (name "Net-(D2-A)") (class "Default")
      (node (ref "D2") (pin "2") (pinfunction "A_2") (pintype "passive"))
      (node (ref "Q1") (pin "1") (pinfunction "G_1") (pintype "passive"))
      (node (ref "R1") (pin "2") (pinfunction "2_2") (pintype "passive"))
      (node (ref "R4") (pin "2") (pinfunction "2_2") (pintype "passive"))
    )
    (net (code "22") (name "Net-(D2-K)") (class "Default")
      (node (ref "D2") (pin "1") (pinfunction "K_1") (pintype "passive"))
      (node (ref "R1") (pin "1") (pinfunction "1_1") (pintype "passive"))
      (node (ref "R9") (pin "2") (pinfunction "2_2") (pintype "passive"))
    )
    (net (code "23") (name "Net-(D3-A)") (class "Default")
      (node (ref "BR1") (pin "3") (pinfunction "AC~_3") (pintype "passive"))
      (node (ref "D3") (pin "1") (pinfunction "A_1") (pintype "passive"))
      (node (ref "L3") (pin "3") (pinfunction "3_3") (pintype "passive"))
    )
    (net (code "24") (name "Net-(D4-A)") (class "Default")
      (node (ref "BR1") (pin "2") (pinfunction "AC~_2") (pintype "passive"))
      (node (ref "D4") (pin "1") (pinfunction "A_1") (pintype "passive"))
      (node (ref "L3") (pin "4") (pinfunction "4_4") (pintype "passive"))
    )
    (net (code "25") (name "Net-(D5-A)") (class "Default")
      (node (ref "D5") (pin "2") (pinfunction "A_2") (pintype "passive"))
      (node (ref "Q3") (pin "3") (pinfunction "S_3") (pintype "passive"))
      (node (ref "T2") (pin "3") (pinfunction "3_3") (pintype "passive"))
    )
    (net (code "26") (name "Net-(D6-A)") (class "Default")
      (node (ref "D6") (pin "2") (pinfunction "A_2") (pintype "passive"))
      (node (ref "Q3") (pin "1") (pinfunction "G_1") (pintype "passive"))
      (node (ref "R10") (pin "2") (pinfunction "2_2") (pintype "passive"))
      (node (ref "R11") (pin "2") (pinfunction "2_2") (pintype "passive"))
    )
    (net (code "27") (name "Net-(D6-K)") (class "Default")
      (node (ref "D6") (pin "1") (pinfunction "K_1") (pintype "passive"))
      (node (ref "R10") (pin "1") (pinfunction "1_1") (pintype "passive"))
      (node (ref "R7") (pin "2") (pinfunction "2_2") (pintype "passive"))
    )
    (net (code "28") (name "Net-(D7-K)") (class "Default")
      (node (ref "D7") (pin "1") (pinfunction "K_1") (pintype "passive"))
      (node (ref "R16") (pin "1") (pinfunction "1_1") (pintype "passive"))
      (node (ref "U3") (pin "4") (pinfunction "IN-_4") (pintype "passive"))
    )
    (net (code "29") (name "Net-(Q2-D)") (class "Default")
      (node (ref "C2") (pin "2") (pintype "passive"))
      (node (ref "Q2") (pin "2") (pinfunction "D_2") (pintype "passive"))
      (node (ref "R78") (pin "2") (pinfunction "2_2") (pintype "passive"))
    )
    (net (code "30") (name "Net-(Q2-G)") (class "Default")
      (node (ref "Q2") (pin "1") (pinfunction "G_1") (pintype "passive"))
      (node (ref "R5") (pin "2") (pinfunction "2_2") (pintype "passive"))
      (node (ref "R6") (pin "2") (pinfunction "2_2") (pintype "passive"))
    )
    (net (code "31") (name "Net-(R13-Pad2)") (class "Default")
      (node (ref "R13") (pin "2") (pinfunction "2_2") (pintype "passive"))
      (node (ref "R17") (pin "1") (pinfunction "1_1") (pintype "passive"))
    )
    (net (code "32") (name "Net-(R15-Pad1)") (class "Default")
      (node (ref "R15") (pin "1") (pinfunction "1_1") (pintype "passive"))
      (node (ref "R18") (pin "2") (pinfunction "2_2") (pintype "passive"))
    )
    (net (code "33") (name "Net-(R17-Pad2)") (class "Default")
      (node (ref "R17") (pin "2") (pinfunction "2_2") (pintype "passive"))
      (node (ref "R21") (pin "2") (pinfunction "2_2") (pintype "passive"))
    )
    (net (code "34") (name "Net-(R18-Pad1)") (class "Default")
      (node (ref "R18") (pin "1") (pinfunction "1_1") (pintype "passive"))
      (node (ref "R23") (pin "2") (pinfunction "2_2") (pintype "passive"))
    )
    (net (code "35") (name "Net-(R19-Pad2)") (class "Default")
      (node (ref "R19") (pin "2") (pinfunction "2_2") (pintype "passive"))
      (node (ref "R20") (pin "1") (pinfunction "1_1") (pintype "passive"))
    )
    (net (code "36") (name "Net-(R34-Pad2)") (class "Default")
      (node (ref "R34") (pin "2") (pinfunction "2_2") (pintype "passive"))
      (node (ref "R35") (pin "1") (pinfunction "1_1") (pintype "passive"))
    )
    (net (code "37") (name "Net-(R35-Pad2)") (class "Default")
      (node (ref "R35") (pin "2") (pinfunction "2_2") (pintype "passive"))
      (node (ref "R36") (pin "1") (pinfunction "1_1") (pintype "passive"))
    )
    (net (code "38") (name "Net-(U1-IN+)") (class "Default")
      (node (ref "C14") (pin "2") (pinfunction "2_2") (pintype "passive"))
      (node (ref "R8") (pin "2") (pinfunction "2_2") (pintype "passive"))
      (node (ref "U1") (pin "3") (pinfunction "IN+_3") (pintype "passive"))
    )
    (net (code "39") (name "Net-(U1-OUT)") (class "Default")
      (node (ref "R7") (pin "1") (pinfunction "1_1") (pintype "passive"))
      (node (ref "U1") (pin "5") (pinfunction "OUT_5") (pintype "passive"))
    )
    (net (code "40") (name "Net-(U2-IN+)") (class "Default")
      (node (ref "C16") (pin "2") (pinfunction "2_2") (pintype "passive"))
      (node (ref "R12") (pin "2") (pinfunction "2_2") (pintype "passive"))
      (node (ref "U2") (pin "3") (pinfunction "IN+_3") (pintype "passive"))
    )
    (net (code "41") (name "Net-(U2-OUT)") (class "Default")
      (node (ref "R9") (pin "1") (pinfunction "1_1") (pintype "passive"))
      (node (ref "U2") (pin "5") (pinfunction "OUT_5") (pintype "passive"))
    )
    (net (code "42") (name "Net-(U3-IN+)") (class "Default")
      (node (ref "C20") (pin "2") (pinfunction "2_2") (pintype "passive"))
      (node (ref "R20") (pin "2") (pinfunction "2_2") (pintype "passive"))
      (node (ref "R24") (pin "2") (pinfunction "2_2") (pintype "passive"))
      (node (ref "R79") (pin "1") (pinfunction "1_1") (pintype "passive"))
      (node (ref "U3") (pin "3") (pinfunction "IN+_3") (pintype "passive"))
    )
    (net (code "43") (name "Net-(U4-BRST)") (class "Default")
      (node (ref "C25") (pin "2") (pinfunction "2_2") (pintype "passive"))
      (node (ref "R29") (pin "1") (pinfunction "1_1") (pintype "passive"))
      (node (ref "R30") (pin "1") (pinfunction "1_1") (pintype "passive"))
      (node (ref "U4") (pin "9") (pinfunction "BRST_9") (pintype "passive"))
    )
    (net (code "44") (name "Net-(U4-CS)") (class "Default")
      (node (ref "C24") (pin "2") (pinfunction "2_2") (pintype "passive"))
      (node (ref "R28") (pin "1") (pinfunction "1_1") (pintype "passive"))
      (node (ref "U4") (pin "10") (pinfunction "CS_10") (pintype "passive"))
    )
    (net (code "45") (name "Net-(U4-HVSEN)") (class "Default")
      (node (ref "C29") (pin "2") (pinfunction "2_2") (pintype "passive"))
      (node (ref "R34") (pin "1") (pinfunction "1_1") (pintype "passive"))
      (node (ref "R37") (pin "2") (pinfunction "2_2") (pintype "passive"))
      (node (ref "U4") (pin "8") (pinfunction "HVSEN_8") (pintype "passive"))
    )
    (net (code "46") (name "Net-(U4-PHB)") (class "Default")
      (node (ref "C27") (pin "2") (pinfunction "2_2") (pintype "passive"))
      (node (ref "R31") (pin "2") (pinfunction "2_2") (pintype "passive"))
      (node (ref "R33") (pin "2") (pinfunction "2_2") (pintype "passive"))
      (node (ref "U4") (pin "4") (pinfunction "PHB_4") (pintype "passive"))
    )
    (net (code "47") (name "Net-(U4-TSET)") (class "Default")
      (node (ref "R25") (pin "2") (pinfunction "2_2") (pintype "passive"))
      (node (ref "U4") (pin "3") (pinfunction "TSET_3") (pintype "passive"))
    )
    (net (code "48") (name "Net-(U4-VINAC)") (class "Default")
      (node (ref "C26") (pin "2") (pinfunction "2_2") (pintype "passive"))
      (node (ref "R21") (pin "1") (pinfunction "1_1") (pintype "passive"))
      (node (ref "R32") (pin "2") (pinfunction "2_2") (pintype "passive"))
      (node (ref "U4") (pin "7") (pinfunction "VINAC_7") (pintype "passive"))
    )
    (net (code "49") (name "Net-(U4-VREF)") (class "Default")
      (node (ref "C28") (pin "2") (pinfunction "2_2") (pintype "passive"))
      (node (ref "R30") (pin "2") (pinfunction "2_2") (pintype "passive"))
      (node (ref "R31") (pin "1") (pinfunction "1_1") (pintype "passive"))
      (node (ref "U4") (pin "15") (pinfunction "VREF_15") (pintype "passive"))
    )
    (net (code "50") (name "Net-(U4-VSENSE)") (class "Default")
      (node (ref "C22") (pin "2") (pinfunction "2_2") (pintype "passive"))
      (node (ref "R23") (pin "1") (pinfunction "1_1") (pintype "passive"))
      (node (ref "R26") (pin "2") (pinfunction "2_2") (pintype "passive"))
      (node (ref "U4") (pin "2") (pinfunction "VSENSE_2") (pintype "passive"))
    )
    (net (code "51") (name "Net-(U4-ZCD_A)") (class "Default")
      (node (ref "C17") (pin "2") (pinfunction "2_2") (pintype "passive"))
      (node (ref "R14") (pin "1") (pinfunction "1_1") (pintype "passive"))
      (node (ref "U4") (pin "16") (pinfunction "ZCD_A_16") (pintype "passive"))
    )
    (net (code "52") (name "Net-(U4-ZCD_B)") (class "Default")
      (node (ref "C21") (pin "2") (pinfunction "2_2") (pintype "passive"))
      (node (ref "R22") (pin "1") (pinfunction "1_1") (pintype "passive"))
      (node (ref "U4") (pin "1") (pinfunction "ZCD_B_1") (pintype "passive"))
    )
    (net (code "54") (name "PGND") (class "Default")
      (node (ref "C1") (pin "1") (pinfunction "1_1") (pintype "passive"))
      (node (ref "C12") (pin "1") (pinfunction "1_1") (pintype "passive"))
      (node (ref "C13") (pin "1") (pinfunction "1_1") (pintype "passive"))
      (node (ref "C14") (pin "1") (pinfunction "1_1") (pintype "passive"))
      (node (ref "C15") (pin "1") (pinfunction "1_1") (pintype "passive"))
      (node (ref "C16") (pin "1") (pinfunction "1_1") (pintype "passive"))
      (node (ref "C17") (pin "1") (pinfunction "1_1") (pintype "passive"))
      (node (ref "C18") (pin "1") (pinfunction "1_1") (pintype "passive"))
      (node (ref "C19") (pin "1") (pinfunction "1_1") (pintype "passive"))
      (node (ref "C20") (pin "1") (pinfunction "1_1") (pintype "passive"))
      (node (ref "C21") (pin "1") (pinfunction "1_1") (pintype "passive"))
      (node (ref "C22") (pin "1") (pinfunction "1_1") (pintype "passive"))
      (node (ref "C23") (pin "1") (pinfunction "1_1") (pintype "passive"))
      (node (ref "C24") (pin "1") (pinfunction "1_1") (pintype "passive"))
      (node (ref "C25") (pin "1") (pinfunction "1_1") (pintype "passive"))
      (node (ref "C26") (pin "1") (pinfunction "1_1") (pintype "passive"))
      (node (ref "C27") (pin "1") (pinfunction "1_1") (pintype "passive"))
      (node (ref "C28") (pin "1") (pinfunction "1_1") (pintype "passive"))
      (node (ref "C29") (pin "1") (pinfunction "1_1") (pintype "passive"))
      (node (ref "C36") (pin "1") (pinfunction "1_1") (pintype "passive"))
      (node (ref "D7") (pin "2") (pinfunction "A_2") (pintype "passive"))
      (node (ref "Q1") (pin "2") (pinfunction "D_2") (pintype "passive"))
      (node (ref "Q2") (pin "3") (pinfunction "S_3") (pintype "passive"))
      (node (ref "Q3") (pin "2") (pinfunction "D_2") (pintype "passive"))
      (node (ref "R11") (pin "1") (pinfunction "1_1") (pintype "passive"))
      (node (ref "R2") (pin "1") (pinfunction "1_1") (pintype "passive"))
      (node (ref "R24") (pin "1") (pinfunction "1_1") (pintype "passive"))
      (node (ref "R25") (pin "1") (pinfunction "1_1") (pintype "passive"))
      (node (ref "R26") (pin "1") (pinfunction "1_1") (pintype "passive"))
      (node (ref "R29") (pin "2") (pinfunction "2_2") (pintype "passive"))
      (node (ref "R3") (pin "1") (pinfunction "1_1") (pintype "passive"))
      (node (ref "R32") (pin "1") (pinfunction "1_1") (pintype "passive"))
      (node (ref "R33") (pin "1") (pinfunction "1_1") (pintype "passive"))
      (node (ref "R37") (pin "1") (pinfunction "1_1") (pintype "passive"))
      (node (ref "R4") (pin "1") (pinfunction "1_1") (pintype "passive"))
      (node (ref "R6") (pin "1") (pinfunction "1_1") (pintype "passive"))
      (node (ref "R78") (pin "1") (pinfunction "1_1") (pintype "passive"))
      (node (ref "T1") (pin "2") (pinfunction "2_2") (pintype "passive"))
      (node (ref "T2") (pin "2") (pinfunction "2_2") (pintype "passive"))
      (node (ref "U1") (pin "2") (pinfunction "GND_2") (pintype "passive"))
      (node (ref "U1") (pin "4") (pinfunction "IN-_4") (pintype "passive"))
      (node (ref "U2") (pin "2") (pinfunction "GND_2") (pintype "passive"))
      (node (ref "U2") (pin "4") (pinfunction "IN-_4") (pintype "passive"))
      (node (ref "U3") (pin "2") (pinfunction "V-_2") (pintype "power_in"))
      (node (ref "U4") (pin "13") (pinfunction "PGND_13") (pintype "passive"))
      (node (ref "U4") (pin "6") (pinfunction "AGND_6") (pintype "passive"))
    )
  )
)
